# display_module.net
KiCad netlist of a schematic drawn in EasyEDA Pro
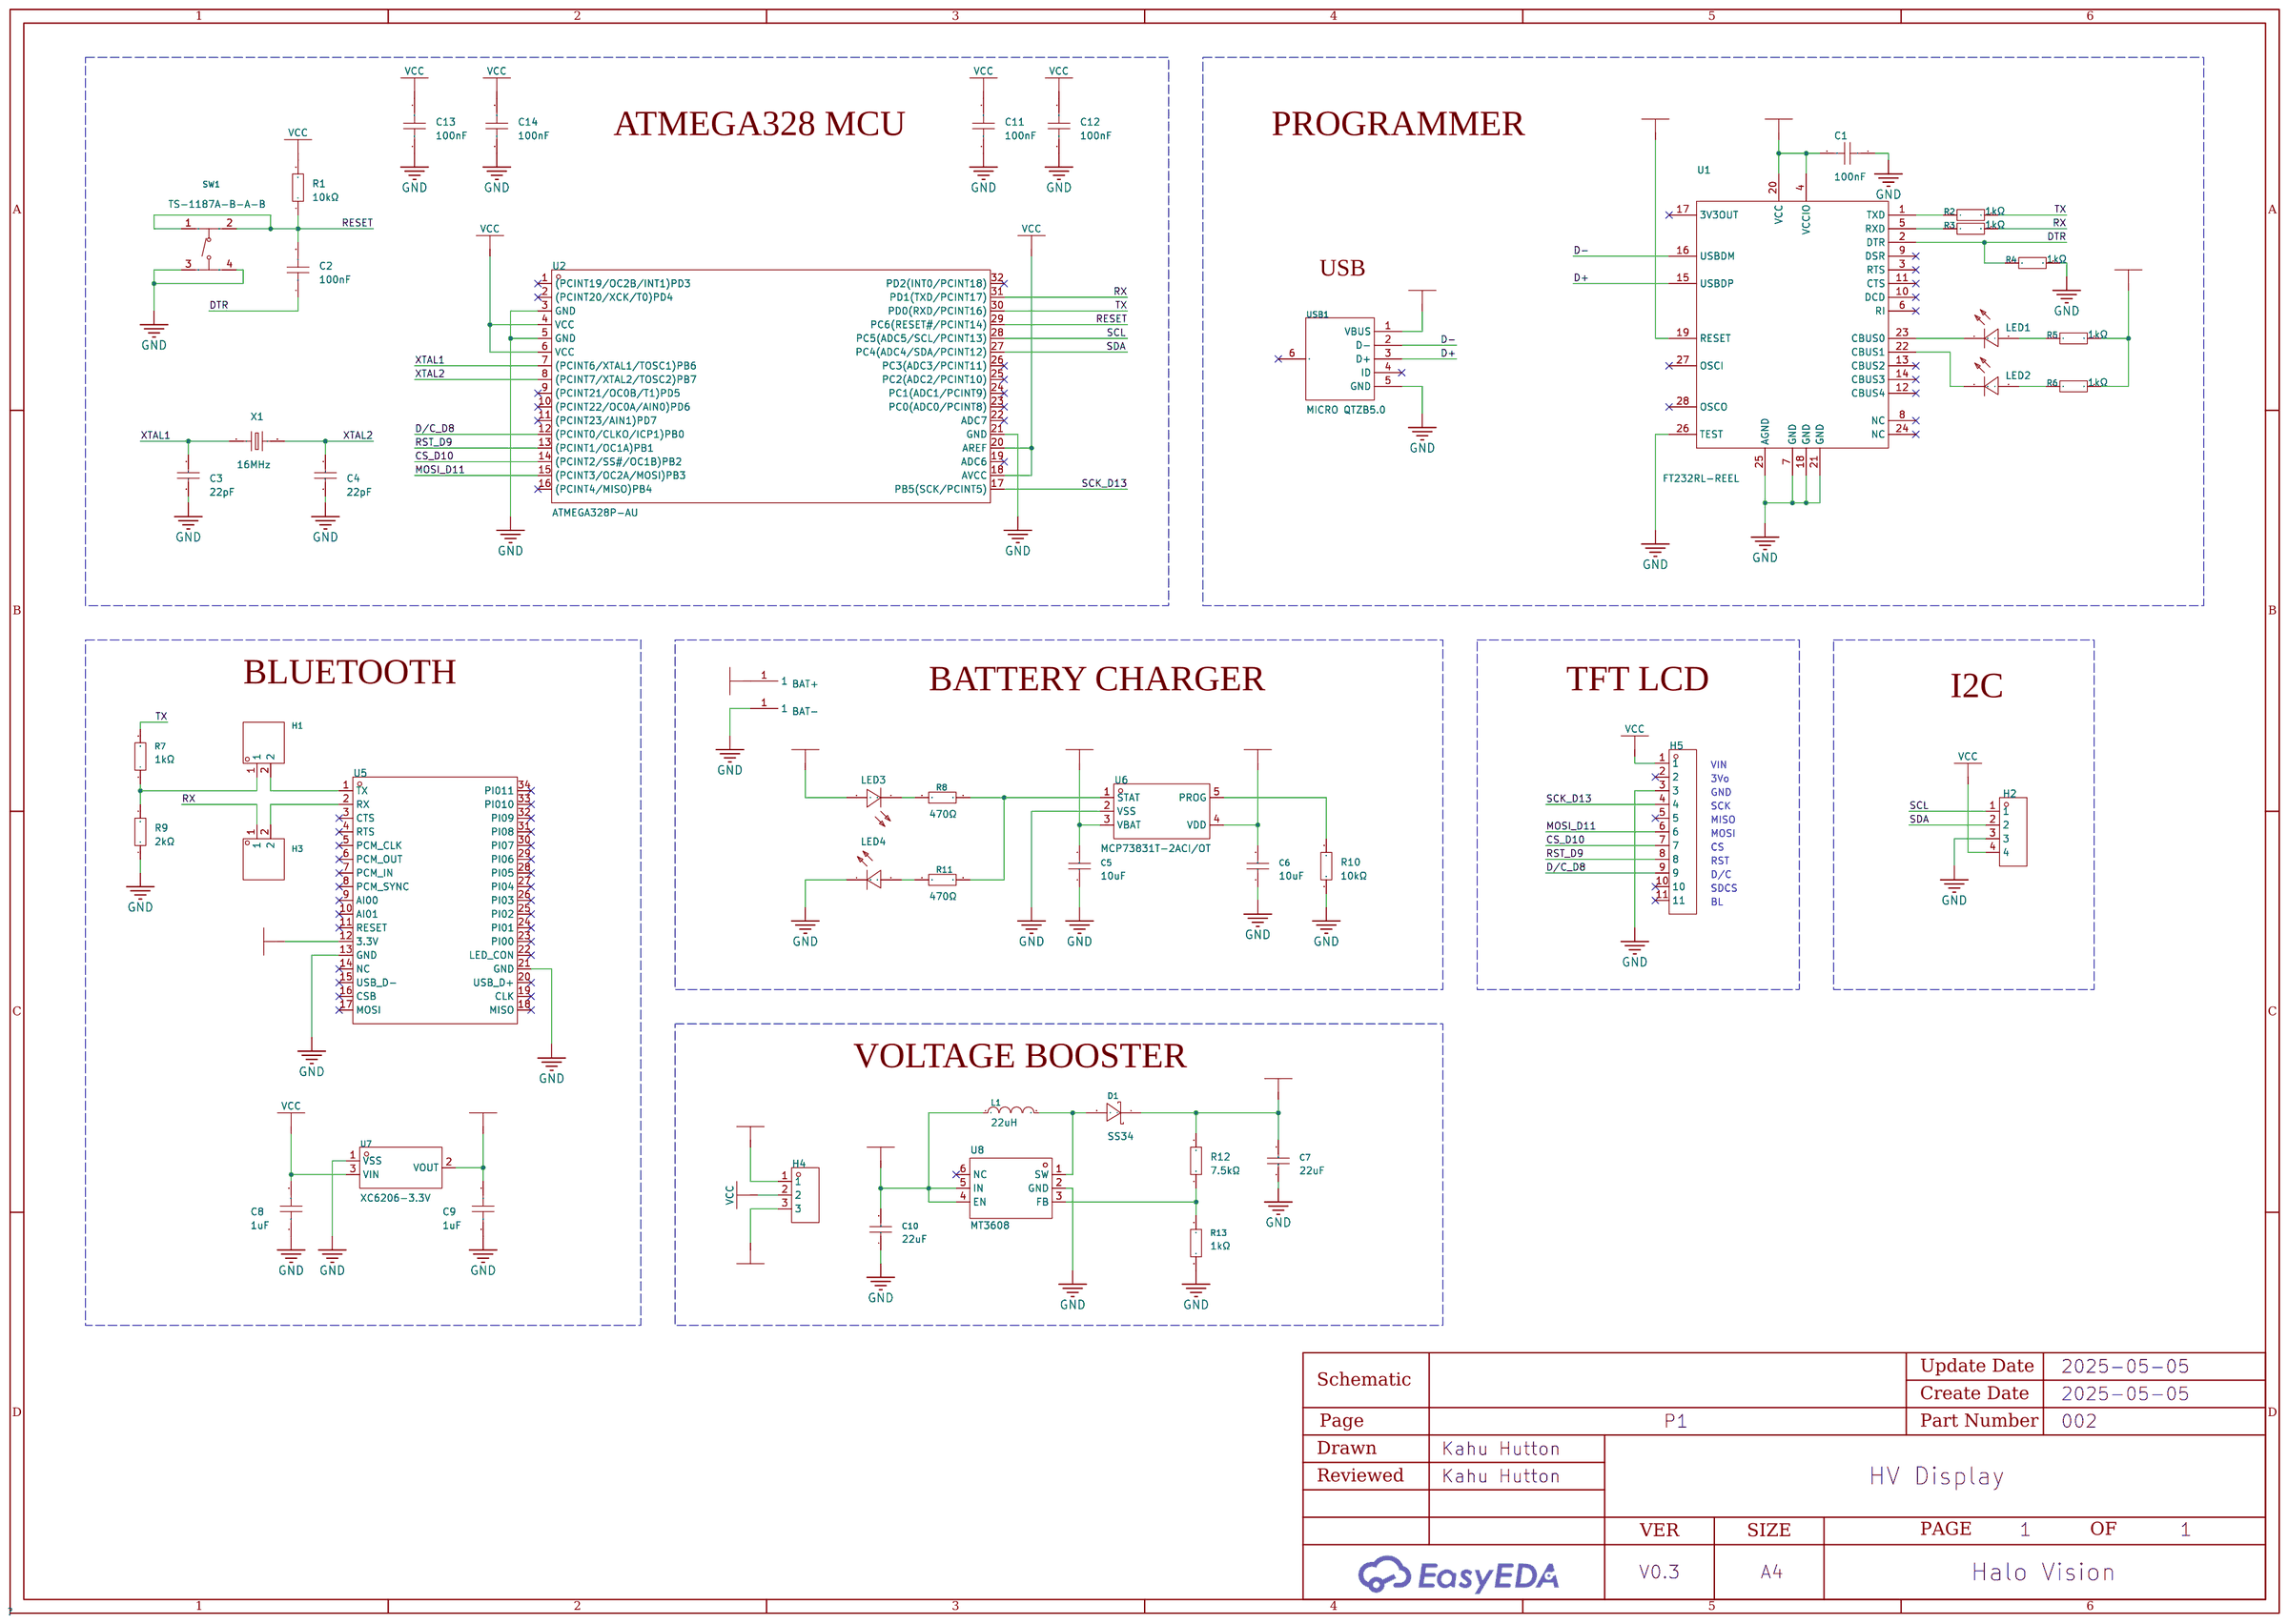
[diagram p0: schematic sheet]

(export (version "E")
  (design (tool "Eeschema 10.0.6"))
  (components
    (comp (ref "C1")
      (value "100nF")
      (footprint "easyedapro:C0402")
      (fields
        (field (name "Manufacturer Part") "CL05B104KB54PNC")
        (field (name "Manufacturer") "SAMSUNG(三星)")
      )
      (libsource (lib "easyedapro") (part "CL05B104KB54PNC"))
    )
    (comp (ref "C2")
      (value "100nF")
      (footprint "easyedapro:C0402")
      (fields
        (field (name "Manufacturer Part") "CL05B104KB54PNC")
        (field (name "Manufacturer") "SAMSUNG(三星)")
      )
      (libsource (lib "easyedapro") (part "CL05B104KB54PNC"))
    )
    (comp (ref "C3")
      (value "22pF")
      (footprint "easyedapro:C0402")
      (fields (field (name "Manufacturer Part") "0402CG220J500NT") (field (name "Manufacturer") "FH(风华)"))
      (libsource (lib "easyedapro") (part "0402CG220J500NT"))
    )
    (comp (ref "C4")
      (value "22pF")
      (footprint "easyedapro:C0402")
      (fields (field (name "Manufacturer Part") "0402CG220J500NT") (field (name "Manufacturer") "FH(风华)"))
      (libsource (lib "easyedapro") (part "0402CG220J500NT"))
    )
    (comp (ref "C5")
      (value "10uF")
      (footprint "easyedapro:C0402")
      (fields
        (field (name "Manufacturer Part") "CL05A106MQ5NUNC")
        (field (name "Manufacturer") "SAMSUNG(三星)")
      )
      (libsource (lib "easyedapro") (part "CL05A106MQ5NUNC"))
    )
    (comp (ref "C6")
      (value "10uF")
      (footprint "easyedapro:C0402")
      (fields
        (field (name "Manufacturer Part") "CL05A106MQ5NUNC")
        (field (name "Manufacturer") "SAMSUNG(三星)")
      )
      (libsource (lib "easyedapro") (part "CL05A106MQ5NUNC"))
    )
    (comp (ref "C7")
      (value "22uF")
      (footprint "easyedapro:C1812")
      (fields (field (name "Manufacturer Part") "1812X226K250NT") (field (name "Manufacturer") "FH(风华)"))
      (libsource (lib "easyedapro") (part "1812X226K250NT"))
    )
    (comp (ref "C8")
      (value "1uF")
      (footprint "easyedapro:C0402")
      (fields
        (field (name "Manufacturer Part") "CL05A105KA5NQNC")
        (field (name "Manufacturer") "SAMSUNG(三星)")
      )
      (libsource (lib "easyedapro") (part "CL05A105KA5NQNC"))
    )
    (comp (ref "C9")
      (value "1uF")
      (footprint "easyedapro:C0402")
      (fields
        (field (name "Manufacturer Part") "CL05A105KA5NQNC")
        (field (name "Manufacturer") "SAMSUNG(三星)")
      )
      (libsource (lib "easyedapro") (part "CL05A105KA5NQNC"))
    )
    (comp (ref "C10")
      (value "22uF")
      (footprint "easyedapro:C1812")
      (fields (field (name "Manufacturer Part") "1812X226K250NT") (field (name "Manufacturer") "FH(风华)"))
      (libsource (lib "easyedapro") (part "1812X226K250NT"))
    )
    (comp (ref "C11")
      (value "100nF")
      (footprint "easyedapro:C0402")
      (fields
        (field (name "Manufacturer Part") "CL05B104KB54PNC")
        (field (name "Manufacturer") "SAMSUNG(三星)")
      )
      (libsource (lib "easyedapro") (part "CL05B104KB54PNC"))
    )
    (comp (ref "C12")
      (value "100nF")
      (footprint "easyedapro:C0402")
      (fields
        (field (name "Manufacturer Part") "CL05B104KB54PNC")
        (field (name "Manufacturer") "SAMSUNG(三星)")
      )
      (libsource (lib "easyedapro") (part "CL05B104KB54PNC"))
    )
    (comp (ref "C13")
      (value "100nF")
      (footprint "easyedapro:C0402")
      (fields
        (field (name "Manufacturer Part") "CL05B104KB54PNC")
        (field (name "Manufacturer") "SAMSUNG(三星)")
      )
      (libsource (lib "easyedapro") (part "CL05B104KB54PNC"))
    )
    (comp (ref "C14")
      (value "100nF")
      (footprint "easyedapro:C0402")
      (fields
        (field (name "Manufacturer Part") "CL05B104KB54PNC")
        (field (name "Manufacturer") "SAMSUNG(三星)")
      )
      (libsource (lib "easyedapro") (part "CL05B104KB54PNC"))
    )
    (comp (ref "D1")
      (value "SS34")
      (footprint "easyedapro:SMA_L4.3-W2.6-LS5.2-RD")
      (fields (field (name "Manufacturer") "MDD"))
      (libsource (lib "easyedapro") (part "SS34_C8678"))
    )
    (comp (ref "H1")
      (value "~")
      (footprint "easyedapro:HDR-TH_2P-P2.54-V-M-1")
      (libsource (lib "easyedapro") (part "210S-1*2P L=11.6MMGold-plated black"))
    )
    (comp (ref "H2")
      (value "~")
      (footprint "easyedapro:HDR-TH_4P-P2.54-V-M")
      (libsource (lib "easyedapro") (part "PZ254V-11-04P"))
    )
    (comp (ref "H3")
      (value "~")
      (footprint "easyedapro:HDR-TH_2P-P2.54-V-M-1")
      (libsource (lib "easyedapro") (part "210S-1*2P L=11.6MMGold-plated black"))
    )
    (comp (ref "H4")
      (value "~")
      (footprint "easyedapro:HDR-TH_3P-P2.54-V-M")
      (libsource (lib "easyedapro") (part "PZ254V-11-03P_C2937625"))
    )
    (comp (ref "H5")
      (value "~")
      (footprint "easyedapro:HDR-TH_11P-P2.54-V-M")
      (libsource (lib "easyedapro") (part "PZ254-1-11-Z-8.5"))
    )
    (comp (ref "L1")
      (value "22uH")
      (footprint "easyedapro:IND-SMD_L7.0-W6.8")
      (fields (field (name "Manufacturer Part") "SMRH74-220MT") (field (name "Manufacturer") "SXN(顺翔诺)"))
      (libsource (lib "easyedapro") (part "SMRH74-220MT"))
    )
    (comp (ref "LED1")
      (value "TJ-S1005SW4TGLC2R-A5")
      (footprint "easyedapro:LED0402-RD")
      (description "Emitted Color:Red")
      (fields (field (name "Manufacturer") "TOGIALED(统佳)"))
      (libsource (lib "easyedapro") (part "TJ-S1005SW4TGLC2R-A5"))
    )
    (comp (ref "LED2")
      (value "TJ-S1005SW4TGLC2R-A5")
      (footprint "easyedapro:LED0402-RD")
      (description "Emitted Color:Red")
      (fields (field (name "Manufacturer") "TOGIALED(统佳)"))
      (libsource (lib "easyedapro") (part "TJ-S1005SW4TGLC2R-A5"))
    )
    (comp (ref "LED3")
      (value "TJ-S1005SW4TGLC2R-A5")
      (footprint "easyedapro:LED0402-RD")
      (description "Emitted Color:Red")
      (fields (field (name "Manufacturer") "TOGIALED(统佳)"))
      (libsource (lib "easyedapro") (part "TJ-S1005SW4TGLC2R-A5"))
    )
    (comp (ref "LED4")
      (value "TJ-S1005SW4TGLC7K-A5")
      (footprint "easyedapro:LED0402-RD_GREEN")
      (description "Emitted Color:Green-yellow")
      (fields (field (name "Manufacturer") "TOGIALED(统佳)"))
      (libsource (lib "easyedapro") (part "TJ-S1005SW4TGLC7K-A5"))
    )
    (comp (ref "R1")
      (value "10kΩ")
      (footprint "easyedapro:R0402")
      (fields
        (field (name "Manufacturer Part") "0402WGF1002TCE")
        (field (name "Manufacturer") "UNI-ROYAL(厚声)")
      )
      (libsource (lib "easyedapro") (part "0402WGF1002TCE"))
    )
    (comp (ref "R2")
      (value "1kΩ")
      (footprint "easyedapro:R0402")
      (fields
        (field (name "Manufacturer Part") "0402WGF1001TCE")
        (field (name "Manufacturer") "UNI-ROYAL(厚声)")
      )
      (libsource (lib "easyedapro") (part "0402WGF1001TCE"))
    )
    (comp (ref "R3")
      (value "1kΩ")
      (footprint "easyedapro:R0402")
      (fields
        (field (name "Manufacturer Part") "0402WGF1001TCE")
        (field (name "Manufacturer") "UNI-ROYAL(厚声)")
      )
      (libsource (lib "easyedapro") (part "0402WGF1001TCE"))
    )
    (comp (ref "R4")
      (value "1kΩ")
      (footprint "easyedapro:R0402")
      (fields
        (field (name "Manufacturer Part") "0402WGF1001TCE")
        (field (name "Manufacturer") "UNI-ROYAL(厚声)")
      )
      (libsource (lib "easyedapro") (part "0402WGF1001TCE"))
    )
    (comp (ref "R5")
      (value "1kΩ")
      (footprint "easyedapro:R0402")
      (fields
        (field (name "Manufacturer Part") "0402WGF1001TCE")
        (field (name "Manufacturer") "UNI-ROYAL(厚声)")
      )
      (libsource (lib "easyedapro") (part "0402WGF1001TCE"))
    )
    (comp (ref "R6")
      (value "1kΩ")
      (footprint "easyedapro:R0402")
      (fields
        (field (name "Manufacturer Part") "0402WGF1001TCE")
        (field (name "Manufacturer") "UNI-ROYAL(厚声)")
      )
      (libsource (lib "easyedapro") (part "0402WGF1001TCE"))
    )
    (comp (ref "R7")
      (value "1kΩ")
      (footprint "easyedapro:R0402")
      (fields
        (field (name "Manufacturer Part") "0402WGF1001TCE")
        (field (name "Manufacturer") "UNI-ROYAL(厚声)")
      )
      (libsource (lib "easyedapro") (part "0402WGF1001TCE"))
    )
    (comp (ref "R8")
      (value "470Ω")
      (footprint "easyedapro:R0402")
      (fields
        (field (name "Manufacturer Part") "0402WGF4700TCE")
        (field (name "Manufacturer") "UNI-ROYAL(厚声)")
      )
      (libsource (lib "easyedapro") (part "0402WGF4700TCE"))
    )
    (comp (ref "R9")
      (value "2kΩ")
      (footprint "easyedapro:R0402")
      (fields
        (field (name "Manufacturer Part") "0402WGF2001TCE")
        (field (name "Manufacturer") "UNI-ROYAL(厚声)")
      )
      (libsource (lib "easyedapro") (part "0402WGF2001TCE"))
    )
    (comp (ref "R10")
      (value "10kΩ")
      (footprint "easyedapro:R0402")
      (fields
        (field (name "Manufacturer Part") "0402WGF1002TCE")
        (field (name "Manufacturer") "UNI-ROYAL(厚声)")
      )
      (libsource (lib "easyedapro") (part "0402WGF1002TCE"))
    )
    (comp (ref "R11")
      (value "470Ω")
      (footprint "easyedapro:R0402")
      (fields
        (field (name "Manufacturer Part") "0402WGF4700TCE")
        (field (name "Manufacturer") "UNI-ROYAL(厚声)")
      )
      (libsource (lib "easyedapro") (part "0402WGF4700TCE"))
    )
    (comp (ref "R12")
      (value "7.5kΩ")
      (footprint "easyedapro:R0402")
      (fields (field (name "Manufacturer Part") "WR04X7501FTL") (field (name "Manufacturer") "Walsin(华新科)"))
      (libsource (lib "easyedapro") (part "WR04X7501FTL"))
    )
    (comp (ref "R13")
      (value "1kΩ")
      (footprint "easyedapro:R0402")
      (fields
        (field (name "Manufacturer Part") "0402WGF1001TCE")
        (field (name "Manufacturer") "UNI-ROYAL(厚声)")
      )
      (libsource (lib "easyedapro") (part "0402WGF1001TCE"))
    )
    (comp (ref "SW1")
      (value "TS-1187A-B-A-B")
      (footprint "easyedapro:SW-SMD_4P-L5.1-W5.1-P3.70-LS6.5-TL-2")
      (fields (field (name "Manufacturer") "XKB Connectivity(中国星坤)"))
      (libsource (lib "easyedapro") (part "TS-1187A-B-A-B"))
    )
    (comp (ref "U1")
      (value "FT232RL-REEL")
      (footprint "easyedapro:SSOP-28_L10.2-W5.3-P0.65-LS7.8-BL")
      (fields (field (name "Manufacturer") "FTDI(飞特帝亚)"))
      (libsource (lib "easyedapro") (part "FT232RL-REEL"))
    )
    (comp (ref "U2")
      (value "ATMEGA328P-AU")
      (footprint "easyedapro:TQFP-32_L7.0-W7.0-P0.80-LS9.0-BL")
      (fields (field (name "Manufacturer") "MICROCHIP(美国微芯)"))
      (libsource (lib "easyedapro") (part "ATMEGA328P-AU"))
    )
    (comp (ref "U3")
      (value "BAT+")
      (footprint "easyedapro:TESTPOINT-TH_BD3.2")
      (fields (field (name "Manufacturer Part") "TP-黑色测试点"))
      (libsource (lib "easyedapro") (part "TP-黑色测试点"))
    )
    (comp (ref "U4")
      (value "BAT-")
      (footprint "easyedapro:TESTPOINT-TH_BD3.2")
      (fields (field (name "Manufacturer Part") "TP-黑色测试点"))
      (libsource (lib "easyedapro") (part "TP-黑色测试点"))
    )
    (comp (ref "U5")
      (value "{ManufacturerPart!}")
      (footprint "easyedapro:BULETM-SMD_HC-05")
      (fields (field (name "Manufacturer Part") "HC-05"))
      (libsource (lib "easyedapro") (part "HC-05"))
    )
    (comp (ref "U6")
      (value "MCP73831T-2ACI/OT")
      (footprint "easyedapro:SOT-23-5_L3.0-W1.7-P0.95-LS2.8-BL")
      (fields (field (name "Manufacturer") "MICROCHIP(美国微芯)"))
      (libsource (lib "easyedapro") (part "MCP73831T-2ACI/OT"))
    )
    (comp (ref "U7")
      (value "XC6206-3.3V")
      (footprint "easyedapro:SSOT-3_L2.9-W1.6-P0.95-LS2.8-BR")
      (fields (field (name "Manufacturer") "YONGYUTAI(永裕泰)"))
      (libsource (lib "easyedapro") (part "XC6206-3.3V"))
    )
    (comp (ref "U8")
      (value "MT3608")
      (footprint "easyedapro:SOT-23-6_L2.9-W1.6-P0.95-LS2.8-BL")
      (fields (field (name "Manufacturer") "西安航天民芯"))
      (libsource (lib "easyedapro") (part "MT3608"))
    )
    (comp (ref "USB1")
      (value "MICRO QTZB5.0")
      (footprint "easyedapro:MICRO-USB-SMD_MICRO-QTZB5.0")
      (fields (field (name "Manufacturer") "SHOU HAN(首韩)"))
      (libsource (lib "easyedapro") (part "MICRO QTZB5.0"))
    )
    (comp (ref "X1")
      (value "16MHz")
      (footprint "easyedapro:HC-49S_L11.4-W4.8")
      (fields (field (name "Manufacturer Part") "TAXM16M2GLFBET2T") (field (name "Manufacturer") "YJX(雅晶鑫)"))
      (libsource (lib "easyedapro") (part "HC-49SM16MHz20pF30ppm"))
    )
  )
  (nets
    (net (code "1") (name "+3V3") (class "Default")
      (node (ref "C9") (pin "2") (pinfunction "2_2") (pintype "unspecified"))
      (node (ref "U5") (pin "12") (pinfunction "3.3V_12") (pintype "input"))
      (node (ref "U7") (pin "2") (pinfunction "VOUT_2") (pintype "input"))
    )
    (net (code "2") (name "/CS_D10") (class "Default")
      (node (ref "H5") (pin "7") (pinfunction "7_7") (pintype "unspecified"))
      (node (ref "U2") (pin "14") (pinfunction "(PCINT2/SS#/OC1B)PB2_14") (pintype "unspecified"))
    )
    (net (code "3") (name "/D+") (class "Default")
      (node (ref "U1") (pin "15") (pinfunction "USBDP_15") (pintype "bidirectional"))
      (node (ref "USB1") (pin "3") (pinfunction "D+_3") (pintype "input"))
    )
    (net (code "4") (name "/D-") (class "Default")
      (node (ref "U1") (pin "16") (pinfunction "USBDM_16") (pintype "bidirectional"))
      (node (ref "USB1") (pin "2") (pinfunction "D-_2") (pintype "input"))
    )
    (net (code "5") (name "/DTR") (class "Default")
      (node (ref "C2") (pin "1") (pinfunction "1_1") (pintype "input"))
      (node (ref "R4") (pin "1") (pinfunction "1_1") (pintype "input"))
      (node (ref "U1") (pin "2") (pinfunction "DTR_2") (pintype "output"))
    )
    (net (code "6") (name "/D{slash}C_D8") (class "Default")
      (node (ref "H5") (pin "9") (pinfunction "9_9") (pintype "unspecified"))
      (node (ref "U2") (pin "12") (pinfunction "(PCINT0/CLKO/ICP1)PB0_12") (pintype "unspecified"))
    )
    (net (code "7") (name "/MOSI_D11") (class "Default")
      (node (ref "H5") (pin "6") (pinfunction "6_6") (pintype "unspecified"))
      (node (ref "U2") (pin "15") (pinfunction "(PCINT3/OC2A/MOSI)PB3_15") (pintype "unspecified"))
    )
    (net (code "8") (name "/RESET") (class "Default")
      (node (ref "C2") (pin "2") (pinfunction "2_2") (pintype "input"))
      (node (ref "R1") (pin "1") (pinfunction "1_1") (pintype "input"))
      (node (ref "SW1") (pin "1") (pinfunction "A_1") (pintype "input"))
      (node (ref "SW1") (pin "2") (pinfunction "B_2") (pintype "input"))
      (node (ref "U2") (pin "29") (pinfunction "PC6(RESET#/PCINT14)_29") (pintype "unspecified"))
    )
    (net (code "9") (name "/RST_D9") (class "Default")
      (node (ref "H5") (pin "8") (pinfunction "8_8") (pintype "unspecified"))
      (node (ref "U2") (pin "13") (pinfunction "(PCINT1/OC1A)PB1_13") (pintype "unspecified"))
    )
    (net (code "10") (name "/RX") (class "Default")
      (node (ref "H3") (pin "1") (pinfunction "1_1") (pintype "input"))
      (node (ref "R3") (pin "2") (pinfunction "2_2") (pintype "input"))
      (node (ref "U2") (pin "31") (pinfunction "PD1(TXD/PCINT17)_31") (pintype "unspecified"))
    )
    (net (code "11") (name "/SCK_D13") (class "Default")
      (node (ref "H5") (pin "4") (pinfunction "4_4") (pintype "unspecified"))
      (node (ref "U2") (pin "17") (pinfunction "PB5(SCK/PCINT5)_17") (pintype "unspecified"))
    )
    (net (code "12") (name "/SCL") (class "Default")
      (node (ref "H2") (pin "1") (pinfunction "1_1") (pintype "unspecified"))
      (node (ref "U2") (pin "28") (pinfunction "PC5(ADC5/SCL/PCINT13)_28") (pintype "unspecified"))
    )
    (net (code "13") (name "/SDA") (class "Default")
      (node (ref "H2") (pin "2") (pinfunction "2_2") (pintype "unspecified"))
      (node (ref "U2") (pin "27") (pinfunction "PC4(ADC4/SDA/PCINT12)_27") (pintype "unspecified"))
    )
    (net (code "14") (name "/TX") (class "Default")
      (node (ref "R2") (pin "2") (pinfunction "2_2") (pintype "input"))
      (node (ref "R7") (pin "2") (pinfunction "2_2") (pintype "input"))
      (node (ref "U2") (pin "30") (pinfunction "PD0(RXD/PCINT16)_30") (pintype "unspecified"))
    )
    (net (code "15") (name "/XTAL1") (class "Default")
      (node (ref "C3") (pin "2") (pinfunction "2_2") (pintype "input"))
      (node (ref "U2") (pin "7") (pinfunction "(PCINT6/XTAL1/TOSC1)PB6_7") (pintype "unspecified"))
      (node (ref "X1") (pin "1") (pinfunction "1_1") (pintype "unspecified"))
    )
    (net (code "16") (name "/XTAL2") (class "Default")
      (node (ref "C4") (pin "2") (pinfunction "2_2") (pintype "input"))
      (node (ref "U2") (pin "8") (pinfunction "(PCINT7/XTAL2/TOSC2)PB7_8") (pintype "unspecified"))
      (node (ref "X1") (pin "2") (pinfunction "2_2") (pintype "unspecified"))
    )
    (net (code "17") (name "5V_BOOST") (class "Default")
      (node (ref "C7") (pin "2") (pinfunction "2_2") (pintype "input"))
      (node (ref "D1") (pin "1") (pinfunction "K_1") (pintype "input"))
      (node (ref "H4") (pin "3") (pinfunction "3_3") (pintype "input"))
      (node (ref "R12") (pin "2") (pinfunction "2_2") (pintype "unspecified"))
    )
    (net (code "18") (name "GND") (class "Default")
      (node (ref "C1") (pin "1") (pinfunction "1_1") (pintype "input"))
      (node (ref "C10") (pin "1") (pinfunction "1_1") (pintype "input"))
      (node (ref "C11") (pin "1") (pinfunction "1_1") (pintype "input"))
      (node (ref "C12") (pin "1") (pinfunction "1_1") (pintype "input"))
      (node (ref "C13") (pin "1") (pinfunction "1_1") (pintype "input"))
      (node (ref "C14") (pin "1") (pinfunction "1_1") (pintype "input"))
      (node (ref "C3") (pin "1") (pinfunction "1_1") (pintype "input"))
      (node (ref "C4") (pin "1") (pinfunction "1_1") (pintype "input"))
      (node (ref "C5") (pin "1") (pinfunction "1_1") (pintype "input"))
      (node (ref "C6") (pin "1") (pinfunction "1_1") (pintype "input"))
      (node (ref "C7") (pin "1") (pinfunction "1_1") (pintype "input"))
      (node (ref "C8") (pin "1") (pinfunction "1_1") (pintype "unspecified"))
      (node (ref "C9") (pin "1") (pinfunction "1_1") (pintype "unspecified"))
      (node (ref "H2") (pin "3") (pinfunction "3_3") (pintype "unspecified"))
      (node (ref "H5") (pin "3") (pinfunction "3_3") (pintype "unspecified"))
      (node (ref "LED4") (pin "1") (pinfunction "C_1") (pintype "unspecified"))
      (node (ref "R10") (pin "1") (pinfunction "1_1") (pintype "input"))
      (node (ref "R13") (pin "1") (pinfunction "1_1") (pintype "input"))
      (node (ref "R4") (pin "2") (pinfunction "2_2") (pintype "input"))
      (node (ref "R9") (pin "1") (pinfunction "1_1") (pintype "input"))
      (node (ref "SW1") (pin "3") (pinfunction "C_3") (pintype "input"))
      (node (ref "SW1") (pin "4") (pinfunction "D_4") (pintype "input"))
      (node (ref "U1") (pin "18") (pinfunction "GND_18") (pintype "unspecified"))
      (node (ref "U1") (pin "21") (pinfunction "GND_21") (pintype "unspecified"))
      (node (ref "U1") (pin "25") (pinfunction "AGND_25") (pintype "unspecified"))
      (node (ref "U1") (pin "26") (pinfunction "TEST_26") (pintype "unspecified"))
      (node (ref "U1") (pin "7") (pinfunction "GND_7") (pintype "unspecified"))
      (node (ref "U2") (pin "21") (pinfunction "GND_21") (pintype "unspecified"))
      (node (ref "U2") (pin "3") (pinfunction "GND_3") (pintype "unspecified"))
      (node (ref "U2") (pin "5") (pinfunction "GND_5") (pintype "unspecified"))
      (node (ref "U4") (pin "1") (pinfunction "1_1") (pintype "input"))
      (node (ref "U5") (pin "13") (pinfunction "GND_13") (pintype "input"))
      (node (ref "U5") (pin "21") (pinfunction "GND_21") (pintype "input"))
      (node (ref "U6") (pin "2") (pinfunction "VSS_2") (pintype "input"))
      (node (ref "U7") (pin "1") (pinfunction "VSS_1") (pintype "input"))
      (node (ref "U8") (pin "2") (pinfunction "GND_2") (pintype "input"))
      (node (ref "USB1") (pin "5") (pinfunction "GND_5") (pintype "input"))
    )
    (net (code "19") (name "Net-(D1-A)") (class "Default")
      (node (ref "D1") (pin "2") (pinfunction "A_2") (pintype "input"))
      (node (ref "L1") (pin "2") (pinfunction "2_2") (pintype "input"))
      (node (ref "U8") (pin "1") (pinfunction "SW_1") (pintype "input"))
    )
    (net (code "20") (name "Net-(H1-Pad1)") (class "Default")
      (node (ref "H1") (pin "1") (pinfunction "1_1") (pintype "input"))
      (node (ref "R7") (pin "1") (pinfunction "1_1") (pintype "input"))
      (node (ref "R9") (pin "2") (pinfunction "2_2") (pintype "input"))
    )
    (net (code "21") (name "Net-(LED1-A)") (class "Default")
      (node (ref "LED1") (pin "2") (pinfunction "A_2") (pintype "unspecified"))
      (node (ref "R5") (pin "1") (pinfunction "1_1") (pintype "input"))
    )
    (net (code "22") (name "Net-(LED1-C)") (class "Default")
      (node (ref "LED1") (pin "1") (pinfunction "C_1") (pintype "unspecified"))
      (node (ref "U1") (pin "23") (pinfunction "CBUS0_23") (pintype "bidirectional"))
    )
    (net (code "23") (name "Net-(LED2-A)") (class "Default")
      (node (ref "LED2") (pin "2") (pinfunction "A_2") (pintype "unspecified"))
      (node (ref "R6") (pin "1") (pinfunction "1_1") (pintype "input"))
    )
    (net (code "24") (name "Net-(LED2-C)") (class "Default")
      (node (ref "LED2") (pin "1") (pinfunction "C_1") (pintype "unspecified"))
      (node (ref "U1") (pin "22") (pinfunction "CBUS1_22") (pintype "bidirectional"))
    )
    (net (code "25") (name "Net-(LED3-C)") (class "Default")
      (node (ref "LED3") (pin "1") (pinfunction "C_1") (pintype "unspecified"))
      (node (ref "R8") (pin "1") (pinfunction "1_1") (pintype "input"))
    )
    (net (code "26") (name "Net-(LED4-A)") (class "Default")
      (node (ref "LED4") (pin "2") (pinfunction "A_2") (pintype "unspecified"))
      (node (ref "R11") (pin "1") (pinfunction "1_1") (pintype "input"))
    )
    (net (code "27") (name "Net-(U1-RXD)") (class "Default")
      (node (ref "R3") (pin "1") (pinfunction "1_1") (pintype "input"))
      (node (ref "U1") (pin "5") (pinfunction "RXD_5") (pintype "unspecified"))
    )
    (net (code "28") (name "Net-(U1-TXD)") (class "Default")
      (node (ref "R2") (pin "1") (pinfunction "1_1") (pintype "input"))
      (node (ref "U1") (pin "1") (pinfunction "TXD_1") (pintype "output"))
    )
    (net (code "29") (name "Net-(U5-RX)") (class "Default")
      (node (ref "H3") (pin "2") (pinfunction "2_2") (pintype "input"))
      (node (ref "U5") (pin "2") (pinfunction "RX_2") (pintype "input"))
    )
    (net (code "30") (name "Net-(U5-TX)") (class "Default")
      (node (ref "H1") (pin "2") (pinfunction "2_2") (pintype "input"))
      (node (ref "U5") (pin "1") (pinfunction "TX_1") (pintype "input"))
    )
    (net (code "31") (name "Net-(U6-PROG)") (class "Default")
      (node (ref "R10") (pin "2") (pinfunction "2_2") (pintype "input"))
      (node (ref "U6") (pin "5") (pinfunction "PROG_5") (pintype "input"))
    )
    (net (code "32") (name "Net-(U6-STAT)") (class "Default")
      (node (ref "R11") (pin "2") (pinfunction "2_2") (pintype "input"))
      (node (ref "R8") (pin "2") (pinfunction "2_2") (pintype "input"))
      (node (ref "U6") (pin "1") (pinfunction "STAT_1") (pintype "input"))
    )
    (net (code "33") (name "Net-(U8-FB)") (class "Default")
      (node (ref "R12") (pin "1") (pinfunction "1_1") (pintype "unspecified"))
      (node (ref "R13") (pin "2") (pinfunction "2_2") (pintype "input"))
      (node (ref "U8") (pin "3") (pinfunction "FB_3") (pintype "input"))
    )
    (net (code "34") (name "VBAT") (class "Default")
      (node (ref "C10") (pin "2") (pinfunction "2_2") (pintype "input"))
      (node (ref "C5") (pin "2") (pinfunction "2_2") (pintype "input"))
      (node (ref "L1") (pin "1") (pinfunction "1_1") (pintype "input"))
      (node (ref "U3") (pin "1") (pinfunction "1_1") (pintype "input"))
      (node (ref "U6") (pin "3") (pinfunction "VBAT_3") (pintype "input"))
      (node (ref "U8") (pin "4") (pinfunction "EN_4") (pintype "input"))
      (node (ref "U8") (pin "5") (pinfunction "IN_5") (pintype "input"))
    )
    (net (code "35") (name "VBUS") (class "Default")
      (node (ref "C1") (pin "2") (pinfunction "2_2") (pintype "input"))
      (node (ref "C6") (pin "2") (pinfunction "2_2") (pintype "input"))
      (node (ref "H4") (pin "1") (pinfunction "1_1") (pintype "input"))
      (node (ref "LED3") (pin "2") (pinfunction "A_2") (pintype "unspecified"))
      (node (ref "R5") (pin "2") (pinfunction "2_2") (pintype "input"))
      (node (ref "R6") (pin "2") (pinfunction "2_2") (pintype "input"))
      (node (ref "U1") (pin "19") (pinfunction "RESET_19") (pintype "unspecified"))
      (node (ref "U1") (pin "20") (pinfunction "VCC_20") (pintype "unspecified"))
      (node (ref "U1") (pin "4") (pinfunction "VCCIO_4") (pintype "unspecified"))
      (node (ref "U6") (pin "4") (pinfunction "VDD_4") (pintype "input"))
      (node (ref "USB1") (pin "1") (pinfunction "VBUS_1") (pintype "input"))
    )
    (net (code "36") (name "VCC") (class "Default")
      (node (ref "C11") (pin "2") (pinfunction "2_2") (pintype "input"))
      (node (ref "C12") (pin "2") (pinfunction "2_2") (pintype "input"))
      (node (ref "C13") (pin "2") (pinfunction "2_2") (pintype "input"))
      (node (ref "C14") (pin "2") (pinfunction "2_2") (pintype "input"))
      (node (ref "C8") (pin "2") (pinfunction "2_2") (pintype "unspecified"))
      (node (ref "H2") (pin "4") (pinfunction "4_4") (pintype "unspecified"))
      (node (ref "H4") (pin "2") (pinfunction "2_2") (pintype "input"))
      (node (ref "H5") (pin "1") (pinfunction "1_1") (pintype "unspecified"))
      (node (ref "R1") (pin "2") (pinfunction "2_2") (pintype "input"))
      (node (ref "U2") (pin "18") (pinfunction "AVCC_18") (pintype "unspecified"))
      (node (ref "U2") (pin "20") (pinfunction "AREF_20") (pintype "unspecified"))
      (node (ref "U2") (pin "4") (pinfunction "VCC_4") (pintype "unspecified"))
      (node (ref "U2") (pin "6") (pinfunction "VCC_6") (pintype "unspecified"))
      (node (ref "U7") (pin "3") (pinfunction "VIN_3") (pintype "input"))
    )
    (net (code "37") (name "unconnected-(H5-Pad2)") (class "Default")
      (node (ref "H5") (pin "2") (pinfunction "2_2") (pintype "unspecified+no_connect"))
    )
    (net (code "38") (name "unconnected-(H5-Pad5)") (class "Default")
      (node (ref "H5") (pin "5") (pinfunction "5_5") (pintype "unspecified+no_connect"))
    )
    (net (code "39") (name "unconnected-(H5-Pad10)") (class "Default")
      (node (ref "H5") (pin "10") (pinfunction "10_10") (pintype "unspecified+no_connect"))
    )
    (net (code "40") (name "unconnected-(H5-Pad11)") (class "Default")
      (node (ref "H5") (pin "11") (pinfunction "11_11") (pintype "unspecified+no_connect"))
    )
    (net (code "41") (name "unconnected-(U1-3V3OUT-Pad17)") (class "Default")
      (node (ref "U1") (pin "17") (pinfunction "3V3OUT_17") (pintype "output+no_connect"))
    )
    (net (code "42") (name "unconnected-(U1-CBUS2-Pad13)") (class "Default")
      (node (ref "U1") (pin "13") (pinfunction "CBUS2_13") (pintype "bidirectional+no_connect"))
    )
    (net (code "43") (name "unconnected-(U1-CBUS3-Pad14)") (class "Default")
      (node (ref "U1") (pin "14") (pinfunction "CBUS3_14") (pintype "bidirectional+no_connect"))
    )
    (net (code "44") (name "unconnected-(U1-CBUS4-Pad12)") (class "Default")
      (node (ref "U1") (pin "12") (pinfunction "CBUS4_12") (pintype "bidirectional+no_connect"))
    )
    (net (code "45") (name "unconnected-(U1-CTS-Pad11)") (class "Default")
      (node (ref "U1") (pin "11") (pinfunction "CTS_11") (pintype "unspecified+no_connect"))
    )
    (net (code "46") (name "unconnected-(U1-DCD-Pad10)") (class "Default")
      (node (ref "U1") (pin "10") (pinfunction "DCD_10") (pintype "unspecified+no_connect"))
    )
    (net (code "47") (name "unconnected-(U1-DSR-Pad9)") (class "Default")
      (node (ref "U1") (pin "9") (pinfunction "DSR_9") (pintype "unspecified+no_connect"))
    )
    (net (code "48") (name "unconnected-(U1-NC-Pad8)") (class "Default")
      (node (ref "U1") (pin "8") (pinfunction "NC_8") (pintype "unspecified+no_connect"))
    )
    (net (code "49") (name "unconnected-(U1-NC-Pad24)") (class "Default")
      (node (ref "U1") (pin "24") (pinfunction "NC_24") (pintype "unspecified+no_connect"))
    )
    (net (code "50") (name "unconnected-(U1-OSCI-Pad27)") (class "Default")
      (node (ref "U1") (pin "27") (pinfunction "OSCI_27") (pintype "unspecified+no_connect"))
    )
    (net (code "51") (name "unconnected-(U1-OSCO-Pad28)") (class "Default")
      (node (ref "U1") (pin "28") (pinfunction "OSCO_28") (pintype "output+no_connect"))
    )
    (net (code "52") (name "unconnected-(U1-RI-Pad6)") (class "Default")
      (node (ref "U1") (pin "6") (pinfunction "RI_6") (pintype "unspecified+no_connect"))
    )
    (net (code "53") (name "unconnected-(U1-RTS-Pad3)") (class "Default")
      (node (ref "U1") (pin "3") (pinfunction "RTS_3") (pintype "output+no_connect"))
    )
    (net (code "54") (name "unconnected-(U2-(PCINT4{slash}MISO)PB4-Pad16)") (class "Default")
      (node (ref "U2") (pin "16") (pinfunction "(PCINT4/MISO)PB4_16") (pintype "unspecified+no_connect"))
    )
    (net (code "55") (name "unconnected-(U2-(PCINT19{slash}OC2B{slash}INT1)PD3-Pad1)") (class "Default")
      (node (ref "U2") (pin "1") (pinfunction "(PCINT19/OC2B/INT1)PD3_1") (pintype "unspecified+no_connect"))
    )
    (net (code "56") (name "unconnected-(U2-(PCINT20{slash}XCK{slash}T0)PD4-Pad2)") (class "Default")
      (node (ref "U2") (pin "2") (pinfunction "(PCINT20/XCK/T0)PD4_2") (pintype "unspecified+no_connect"))
    )
    (net (code "57") (name "unconnected-(U2-(PCINT21{slash}OC0B{slash}T1)PD5-Pad9)") (class "Default")
      (node (ref "U2") (pin "9") (pinfunction "(PCINT21/OC0B/T1)PD5_9") (pintype "unspecified+no_connect"))
    )
    (net (code "58") (name "unconnected-(U2-(PCINT22{slash}OC0A{slash}AIN0)PD6-Pad10)") (class "Default")
      (node (ref "U2") (pin "10") (pinfunction "(PCINT22/OC0A/AIN0)PD6_10") (pintype "unspecified+no_connect"))
    )
    (net (code "59") (name "unconnected-(U2-(PCINT23{slash}AIN1)PD7-Pad11)") (class "Default")
      (node (ref "U2") (pin "11") (pinfunction "(PCINT23/AIN1)PD7_11") (pintype "unspecified+no_connect"))
    )
    (net (code "60") (name "unconnected-(U2-ADC6-Pad19)") (class "Default")
      (node (ref "U2") (pin "19") (pinfunction "ADC6_19") (pintype "unspecified+no_connect"))
    )
    (net (code "61") (name "unconnected-(U2-ADC7-Pad22)") (class "Default")
      (node (ref "U2") (pin "22") (pinfunction "ADC7_22") (pintype "unspecified+no_connect"))
    )
    (net (code "62") (name "unconnected-(U2-PC0(ADC0{slash}PCINT8)-Pad23)") (class "Default")
      (node (ref "U2") (pin "23") (pinfunction "PC0(ADC0/PCINT8)_23") (pintype "unspecified+no_connect"))
    )
    (net (code "63") (name "unconnected-(U2-PC1(ADC1{slash}PCINT9)-Pad24)") (class "Default")
      (node (ref "U2") (pin "24") (pinfunction "PC1(ADC1/PCINT9)_24") (pintype "unspecified+no_connect"))
    )
    (net (code "64") (name "unconnected-(U2-PC2(ADC2{slash}PCINT10)-Pad25)") (class "Default")
      (node (ref "U2") (pin "25") (pinfunction "PC2(ADC2/PCINT10)_25") (pintype "unspecified+no_connect"))
    )
    (net (code "65") (name "unconnected-(U2-PC3(ADC3{slash}PCINT11)-Pad26)") (class "Default")
      (node (ref "U2") (pin "26") (pinfunction "PC3(ADC3/PCINT11)_26") (pintype "unspecified+no_connect"))
    )
    (net (code "66") (name "unconnected-(U2-PD2(INT0{slash}PCINT18)-Pad32)") (class "Default")
      (node (ref "U2") (pin "32") (pinfunction "PD2(INT0/PCINT18)_32") (pintype "unspecified+no_connect"))
    )
    (net (code "67") (name "unconnected-(U5-AI00-Pad9)") (class "Default")
      (node (ref "U5") (pin "9") (pinfunction "AI00_9") (pintype "input+no_connect"))
    )
    (net (code "68") (name "unconnected-(U5-AI01-Pad10)") (class "Default")
      (node (ref "U5") (pin "10") (pinfunction "AI01_10") (pintype "input+no_connect"))
    )
    (net (code "69") (name "unconnected-(U5-CLK-Pad19)") (class "Default")
      (node (ref "U5") (pin "19") (pinfunction "CLK_19") (pintype "input+no_connect"))
    )
    (net (code "70") (name "unconnected-(U5-CSB-Pad16)") (class "Default")
      (node (ref "U5") (pin "16") (pinfunction "CSB_16") (pintype "input+no_connect"))
    )
    (net (code "71") (name "unconnected-(U5-CTS-Pad3)") (class "Default")
      (node (ref "U5") (pin "3") (pinfunction "CTS_3") (pintype "input+no_connect"))
    )
    (net (code "72") (name "unconnected-(U5-LED_CON-Pad22)") (class "Default")
      (node (ref "U5") (pin "22") (pinfunction "LED_CON_22") (pintype "input+no_connect"))
    )
    (net (code "73") (name "unconnected-(U5-MISO-Pad18)") (class "Default")
      (node (ref "U5") (pin "18") (pinfunction "MISO_18") (pintype "input+no_connect"))
    )
    (net (code "74") (name "unconnected-(U5-MOSI-Pad17)") (class "Default")
      (node (ref "U5") (pin "17") (pinfunction "MOSI_17") (pintype "input+no_connect"))
    )
    (net (code "75") (name "unconnected-(U5-NC-Pad14)") (class "Default")
      (node (ref "U5") (pin "14") (pinfunction "NC_14") (pintype "input+no_connect"))
    )
    (net (code "76") (name "unconnected-(U5-PCM_CLK-Pad5)") (class "Default")
      (node (ref "U5") (pin "5") (pinfunction "PCM_CLK_5") (pintype "input+no_connect"))
    )
    (net (code "77") (name "unconnected-(U5-PCM_IN-Pad7)") (class "Default")
      (node (ref "U5") (pin "7") (pinfunction "PCM_IN_7") (pintype "input+no_connect"))
    )
    (net (code "78") (name "unconnected-(U5-PCM_OUT-Pad6)") (class "Default")
      (node (ref "U5") (pin "6") (pinfunction "PCM_OUT_6") (pintype "input+no_connect"))
    )
    (net (code "79") (name "unconnected-(U5-PCM_SYNC-Pad8)") (class "Default")
      (node (ref "U5") (pin "8") (pinfunction "PCM_SYNC_8") (pintype "input+no_connect"))
    )
    (net (code "80") (name "unconnected-(U5-PI00-Pad23)") (class "Default")
      (node (ref "U5") (pin "23") (pinfunction "PI00_23") (pintype "input+no_connect"))
    )
    (net (code "81") (name "unconnected-(U5-PI01-Pad24)") (class "Default")
      (node (ref "U5") (pin "24") (pinfunction "PI01_24") (pintype "input+no_connect"))
    )
    (net (code "82") (name "unconnected-(U5-PI02-Pad25)") (class "Default")
      (node (ref "U5") (pin "25") (pinfunction "PI02_25") (pintype "input+no_connect"))
    )
    (net (code "83") (name "unconnected-(U5-PI03-Pad26)") (class "Default")
      (node (ref "U5") (pin "26") (pinfunction "PI03_26") (pintype "input+no_connect"))
    )
    (net (code "84") (name "unconnected-(U5-PI04-Pad27)") (class "Default")
      (node (ref "U5") (pin "27") (pinfunction "PI04_27") (pintype "input+no_connect"))
    )
    (net (code "85") (name "unconnected-(U5-PI05-Pad28)") (class "Default")
      (node (ref "U5") (pin "28") (pinfunction "PI05_28") (pintype "input+no_connect"))
    )
    (net (code "86") (name "unconnected-(U5-PI06-Pad29)") (class "Default")
      (node (ref "U5") (pin "29") (pinfunction "PI06_29") (pintype "input+no_connect"))
    )
    (net (code "87") (name "unconnected-(U5-PI07-Pad30)") (class "Default")
      (node (ref "U5") (pin "30") (pinfunction "PI07_30") (pintype "input+no_connect"))
    )
    (net (code "88") (name "unconnected-(U5-PI08-Pad31)") (class "Default")
      (node (ref "U5") (pin "31") (pinfunction "PI08_31") (pintype "input+no_connect"))
    )
    (net (code "89") (name "unconnected-(U5-PI09-Pad32)") (class "Default")
      (node (ref "U5") (pin "32") (pinfunction "PI09_32") (pintype "input+no_connect"))
    )
    (net (code "90") (name "unconnected-(U5-PI010-Pad33)") (class "Default")
      (node (ref "U5") (pin "33") (pinfunction "PI010_33") (pintype "input+no_connect"))
    )
    (net (code "91") (name "unconnected-(U5-PI011-Pad34)") (class "Default")
      (node (ref "U5") (pin "34") (pinfunction "PI011_34") (pintype "input+no_connect"))
    )
    (net (code "92") (name "unconnected-(U5-RESET-Pad11)") (class "Default")
      (node (ref "U5") (pin "11") (pinfunction "RESET_11") (pintype "input+no_connect"))
    )
    (net (code "93") (name "unconnected-(U5-RTS-Pad4)") (class "Default")
      (node (ref "U5") (pin "4") (pinfunction "RTS_4") (pintype "input+no_connect"))
    )
    (net (code "94") (name "unconnected-(U5-USB_D+-Pad20)") (class "Default")
      (node (ref "U5") (pin "20") (pinfunction "USB_D+_20") (pintype "input+no_connect"))
    )
    (net (code "95") (name "unconnected-(U5-USB_D--Pad15)") (class "Default")
      (node (ref "U5") (pin "15") (pinfunction "USB_D-_15") (pintype "input+no_connect"))
    )
    (net (code "96") (name "unconnected-(U8-NC-Pad6)") (class "Default")
      (node (ref "U8") (pin "6") (pinfunction "NC_6") (pintype "input+no_connect"))
    )
    (net (code "97") (name "unconnected-(USB1-EH-Pad6)") (class "Default")
      (node (ref "USB1") (pin "6") (pinfunction "EH_6") (pintype "input+no_connect"))
    )
    (net (code "98") (name "unconnected-(USB1-ID-Pad4)") (class "Default")
      (node (ref "USB1") (pin "4") (pinfunction "ID_4") (pintype "input+no_connect"))
    )
  )
)
